# GBASP_USB-C.net
KiCad netlist of a schematic drawn in EAGLE
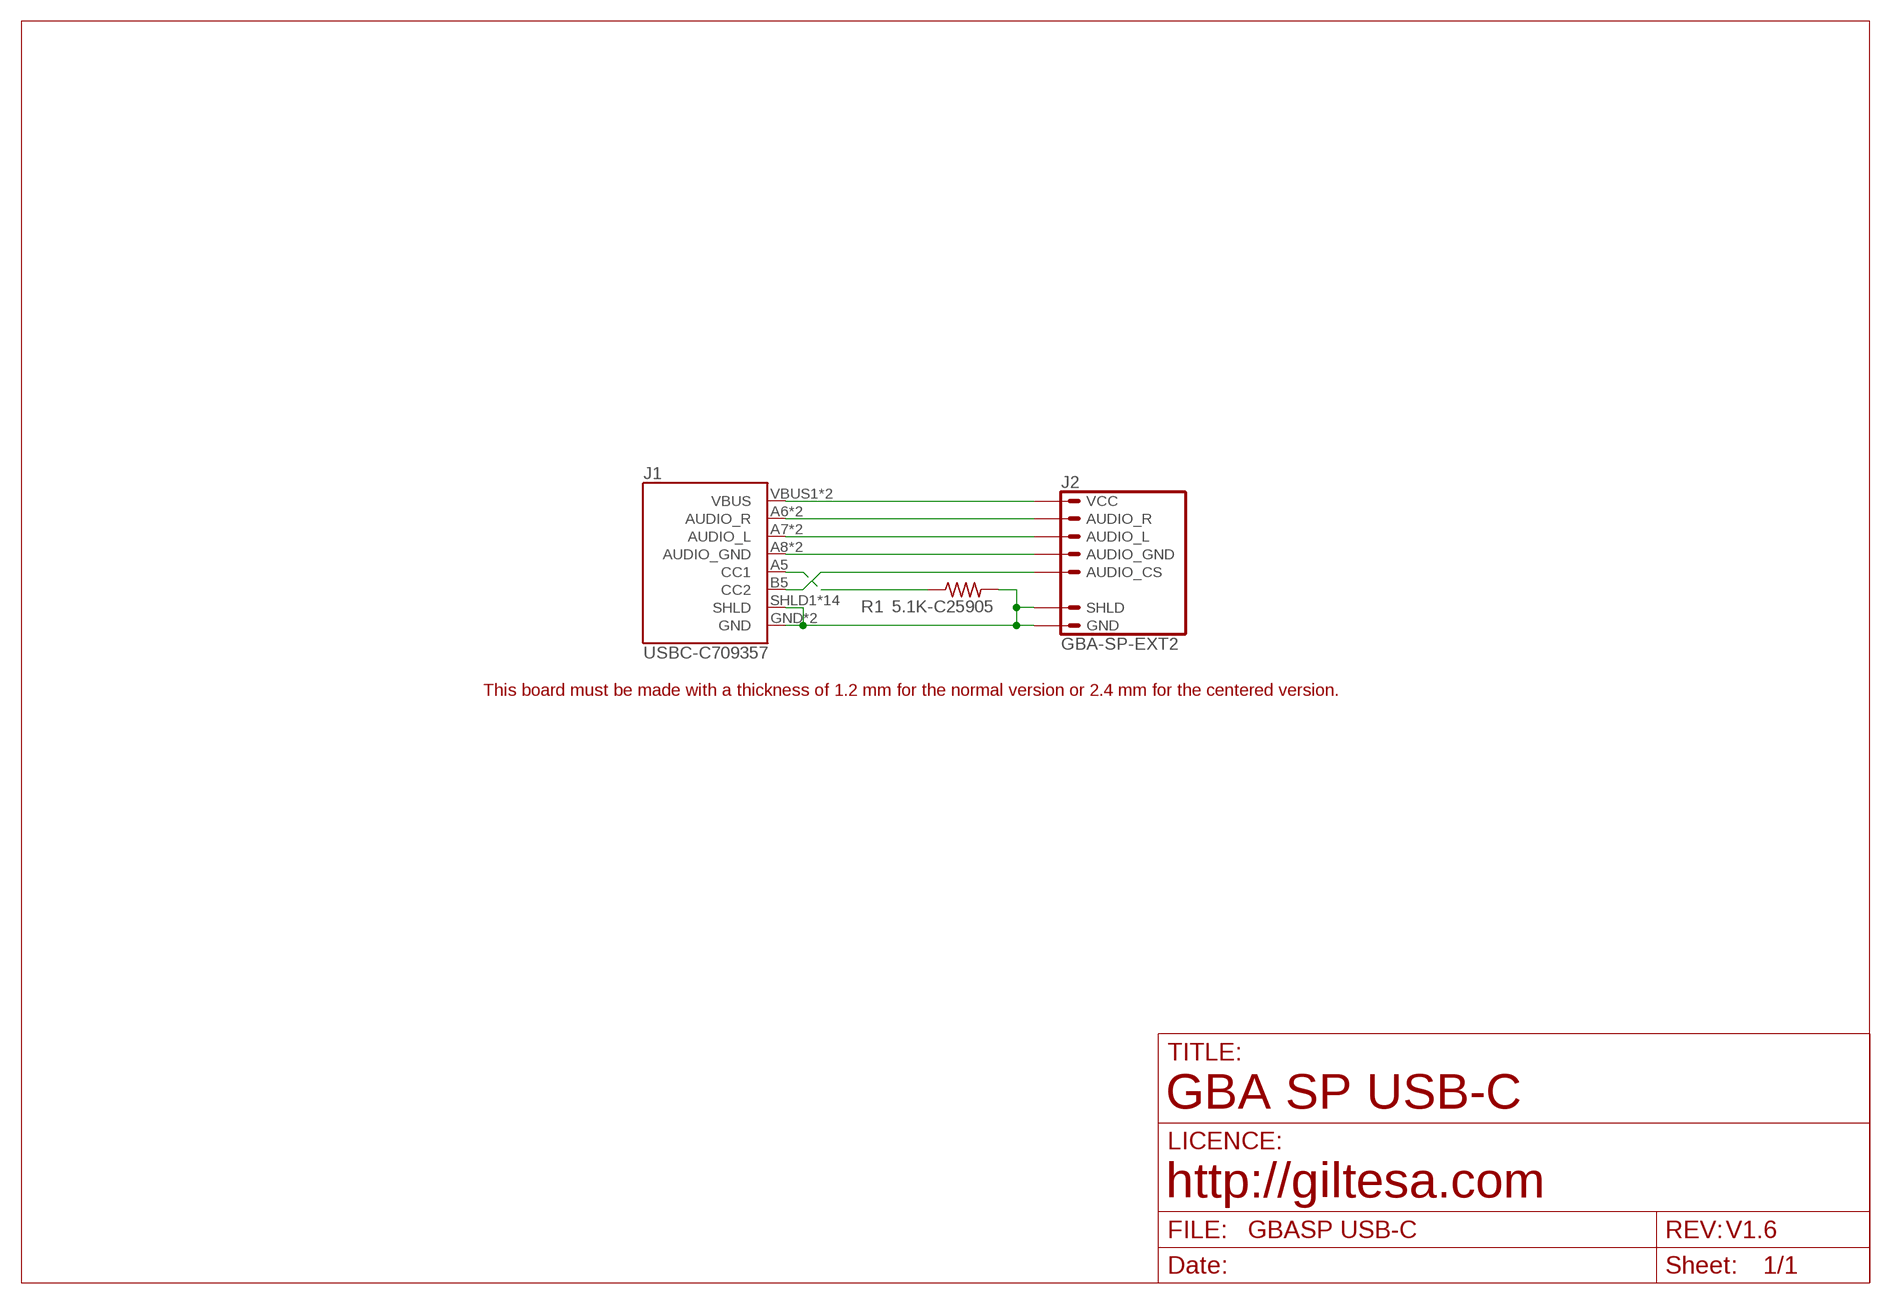
[diagram p0: schematic, sheet 1]

(export (version "E")
  (design (tool "Eeschema 10.0.6"))
  (components
    (comp (ref "J1")
      (value "USBC-C709357")
      (footprint "eagle-import:USB-C_16P_3SHLD_DRILL")
      (libsource (lib "eagle-import") (part "USB-C_POWER_AUDIOGBASP_DRILL"))
    )
    (comp (ref "J2")
      (value "GBA-SP-EXT2")
      (footprint "eagle-import:GBA-SP-EXT2_1")
      (libsource (lib "eagle-import") (part "GBA-SP-EXT2_1"))
    )
    (comp (ref "R1")
      (value "5.1K-C25905")
      (footprint "eagle-import:R0402")
      (libsource (lib "eagle-import") (part "R0402"))
    )
  )
  (nets
    (net (code "1") (name "Net-(J1-AUDIO_GND-PadA8)") (class "Default")
      (node (ref "J1") (pin "A8") (pinfunction "AUDIO_GND_A8") (pintype "bidirectional"))
      (node (ref "J1") (pin "B8") (pinfunction "AUDIO_GND_B8") (pintype "bidirectional"))
      (node (ref "J2") (pin "AUDIO_GND") (pinfunction "AUDIO_GND_AUDIO_GND") (pintype "passive"))
    )
    (net (code "2") (name "Net-(J1-AUDIO_L-PadA7)") (class "Default")
      (node (ref "J1") (pin "A7") (pinfunction "AUDIO_L_A7") (pintype "bidirectional"))
      (node (ref "J1") (pin "B7") (pinfunction "AUDIO_L_B7") (pintype "bidirectional"))
      (node (ref "J2") (pin "AUDIO_L") (pinfunction "AUDIO_L_AUDIO_L") (pintype "passive"))
    )
    (net (code "3") (name "Net-(J1-AUDIO_R-PadA6)") (class "Default")
      (node (ref "J1") (pin "A6") (pinfunction "AUDIO_R_A6") (pintype "bidirectional"))
      (node (ref "J1") (pin "B6") (pinfunction "AUDIO_R_B6") (pintype "bidirectional"))
      (node (ref "J2") (pin "AUDIO_R") (pinfunction "AUDIO_R_AUDIO_R") (pintype "passive"))
    )
    (net (code "4") (name "Net-(J1-CC1)") (class "Default")
      (node (ref "J1") (pin "A5") (pinfunction "CC1_A5") (pintype "bidirectional"))
      (node (ref "R1") (pin "1") (pinfunction "1_1") (pintype "passive"))
    )
    (net (code "5") (name "Net-(J1-CC2)") (class "Default")
      (node (ref "J1") (pin "B5") (pinfunction "CC2_B5") (pintype "bidirectional"))
      (node (ref "J2") (pin "AUDIO_CS") (pinfunction "AUDIO_CS_AUDIO_CS") (pintype "passive"))
    )
    (net (code "6") (name "Net-(J1-GND-PadGND2)") (class "Default")
      (node (ref "J1") (pin "GND") (pinfunction "GND_GND") (pintype "bidirectional"))
      (node (ref "J1") (pin "GND2") (pinfunction "GND_GND2") (pintype "bidirectional"))
      (node (ref "J1") (pin "SHLD1") (pinfunction "SHLD_SHLD1") (pintype "bidirectional"))
      (node (ref "J1") (pin "SHLD1_2") (pinfunction "SHLD_SHLD1_2") (pintype "bidirectional"))
      (node (ref "J1") (pin "SHLD3") (pinfunction "SHLD_SHLD3") (pintype "bidirectional"))
      (node (ref "J1") (pin "SHLD3_2") (pinfunction "SHLD_SHLD3_2") (pintype "bidirectional"))
      (node (ref "J1") (pin "SHLD4") (pinfunction "SHLD_SHLD4") (pintype "bidirectional"))
      (node (ref "J1") (pin "SHLD4_2") (pinfunction "SHLD_SHLD4_2") (pintype "bidirectional"))
      (node (ref "J1") (pin "SHLD5") (pinfunction "SHLD_SHLD5") (pintype "bidirectional"))
      (node (ref "J1") (pin "SHLD5_2") (pinfunction "SHLD_SHLD5_2") (pintype "bidirectional"))
      (node (ref "J1") (pin "SHLD6") (pinfunction "SHLD_SHLD6") (pintype "bidirectional"))
      (node (ref "J1") (pin "SHLD6_2") (pinfunction "SHLD_SHLD6_2") (pintype "bidirectional"))
      (node (ref "J1") (pin "SHLD7") (pinfunction "SHLD_SHLD7") (pintype "bidirectional"))
      (node (ref "J1") (pin "SHLD7_2") (pinfunction "SHLD_SHLD7_2") (pintype "bidirectional"))
      (node (ref "J1") (pin "SHLD8") (pinfunction "SHLD_SHLD8") (pintype "bidirectional"))
      (node (ref "J1") (pin "SHLD8_2") (pinfunction "SHLD_SHLD8_2") (pintype "bidirectional"))
      (node (ref "J2") (pin "GND") (pinfunction "GND_GND") (pintype "passive"))
      (node (ref "J2") (pin "SHLD1") (pinfunction "SHLD_SHLD1") (pintype "passive"))
      (node (ref "J2") (pin "SHLD2") (pinfunction "SHLD_SHLD2") (pintype "passive"))
      (node (ref "J2") (pin "SHLD3") (pinfunction "SHLD_SHLD3") (pintype "passive"))
      (node (ref "J2") (pin "SHLD4") (pinfunction "SHLD_SHLD4") (pintype "passive"))
      (node (ref "R1") (pin "2") (pinfunction "2_2") (pintype "passive"))
    )
    (net (code "7") (name "Net-(J1-VBUS-PadVBUS1)") (class "Default")
      (node (ref "J1") (pin "VBUS1") (pinfunction "VBUS_VBUS1") (pintype "bidirectional"))
      (node (ref "J1") (pin "VBUS2") (pinfunction "VBUS_VBUS2") (pintype "bidirectional"))
      (node (ref "J2") (pin "VCC") (pinfunction "VCC_VCC") (pintype "passive"))
    )
  )
)
